# Digital_to_Analog.net
KiCad netlist of a schematic drawn in Altium Designer
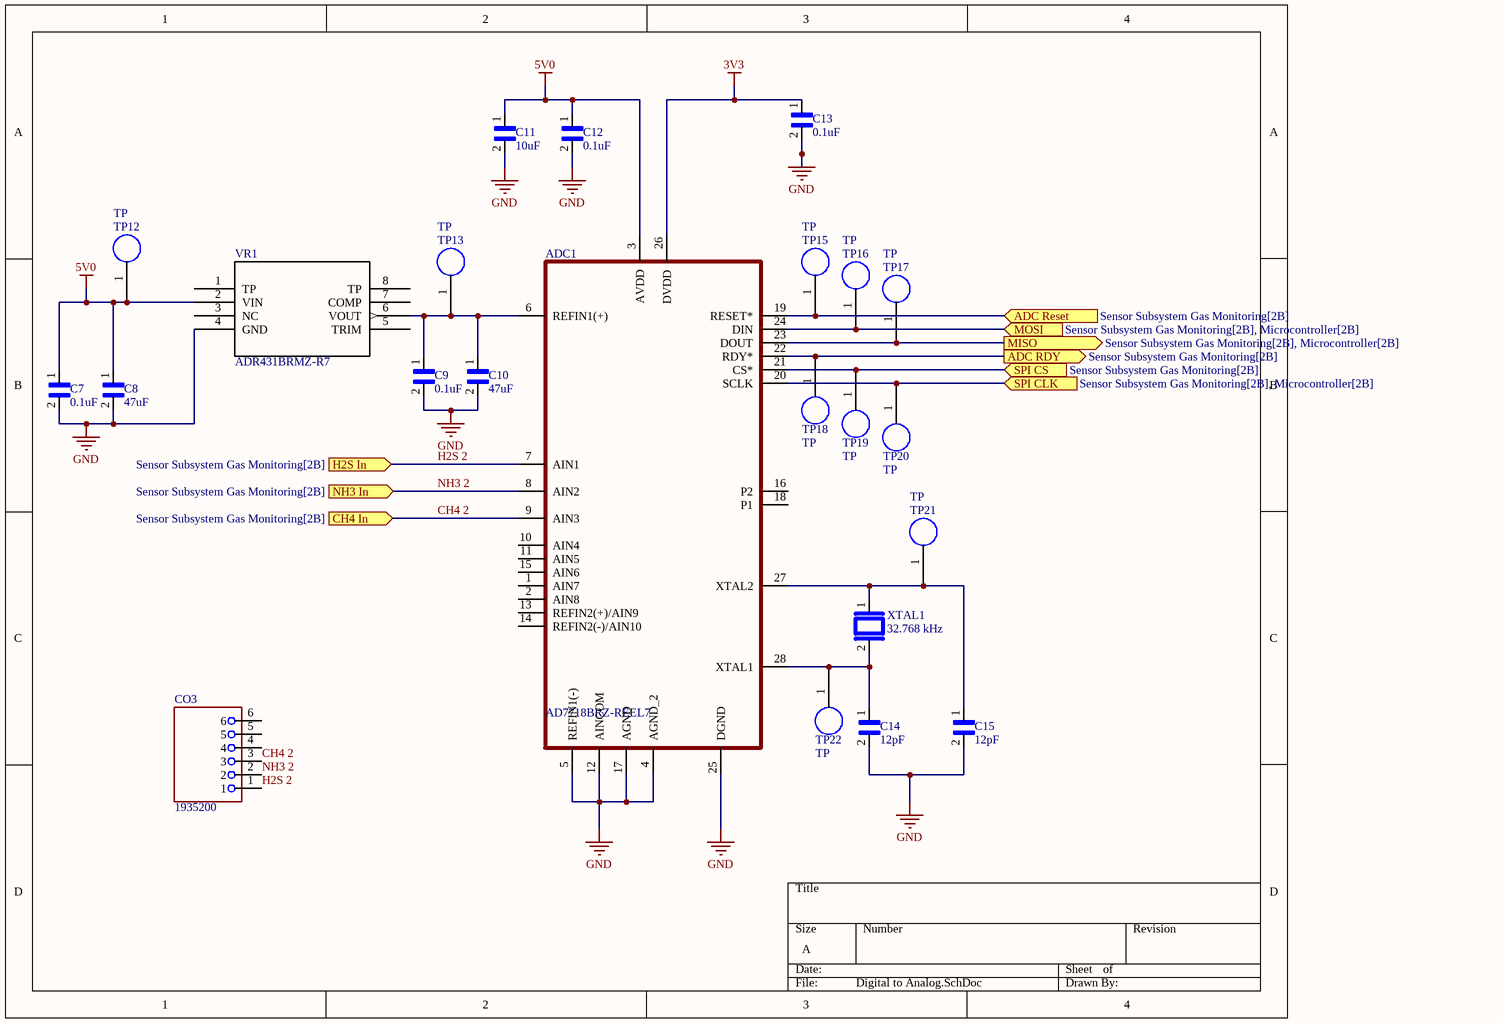
[diagram p0: Digital to Analog.SchDoc]

(export (version "E")
  (design (tool "Eeschema 10.0.6"))
  (components
    (comp (ref "ADC1")
      (value "AD7718BRZ-REEL7")
      (footprint "SOIC127P1032X265-28N")
      (description "24-Bit, 8/10-Channel, Low Voltage, Low Power, Sigma Delta ADC")
      (fields (field (name "MF") "Analog Devices"))
      (libsource (lib "AD7718") (part "AD7718BRZ-REEL7"))
    )
    (comp (ref "C7")
      (value "0.1uF")
      (footprint "0.1uF Capacitor")
      (description "No Description Available")
      (libsource (lib "0.1uF Capacitor") (part "CC1206JRX7R9BB104"))
    )
    (comp (ref "C8")
      (value "47uF")
      (footprint "47uF Capacitor:CAPC2012X135N")
      (description "47ÂµF Â±20% 6.3V Ceramic Capacitor X5R 0805 _2012 Metric_")
      (fields
        (field (name "MF") "Samsung Electro-Mechanics")
        (field (name "DIGI-KEY_PART_NUMBER") "1276-6467-1-ND")
      )
      (libsource (lib "47uF Capacitor") (part "CL21A476MQYNNNG"))
    )
    (comp (ref "C9")
      (value "0.1uF")
      (footprint "0.1uF Capacitor")
      (description "No Description Available")
      (libsource (lib "0.1uF Capacitor") (part "CC1206JRX7R9BB104"))
    )
    (comp (ref "C10")
      (value "47uF")
      (footprint "47uF Capacitor:CAPC2012X135N")
      (description "47ÂµF Â±20% 6.3V Ceramic Capacitor X5R 0805 _2012 Metric_")
      (fields
        (field (name "MF") "Samsung Electro-Mechanics")
        (field (name "DIGI-KEY_PART_NUMBER") "1276-6467-1-ND")
      )
      (libsource (lib "47uF Capacitor") (part "CL21A476MQYNNNG"))
    )
    (comp (ref "C11")
      (value "10uF")
      (footprint "10uF Capacitor:CAPC3216X190N")
      (description "CAP CER 10UF 25V X5R 1206")
      (fields (field (name "MP") "GRJ31CR61E106KE11L"))
      (libsource (lib "10uF Capacitor") (part "GRJ31CR61E106KE11L"))
    )
    (comp (ref "C12")
      (value "0.1uF")
      (footprint "0.1uF Capacitor")
      (description "No Description Available")
      (libsource (lib "0.1uF Capacitor") (part "CC1206JRX7R9BB104"))
    )
    (comp (ref "C13")
      (value "0.1uF")
      (footprint "0.1uF Capacitor")
      (description "No Description Available")
      (libsource (lib "0.1uF Capacitor") (part "CC1206JRX7R9BB104"))
    )
    (comp (ref "C14")
      (value "12pF")
      (footprint "CAPC1608X90N")
      (description "Multilayer Ceramic Capacitor, CGA Series, 12 pF, - 5%, C0G / NP0, 50 V, 0603 [1608 Metric]")
      (fields (field (name "MF") "TDK") (field (name "MP") "CGA3E2C0G1H120J080AA"))
      (libsource (lib "12pF Capacitor") (part "CGA3E2C0G1H120J080AA"))
    )
    (comp (ref "C15")
      (value "12pF")
      (footprint "CAPC1608X90N")
      (description "Multilayer Ceramic Capacitor, CGA Series, 12 pF, - 5%, C0G / NP0, 50 V, 0603 [1608 Metric]")
      (fields (field (name "MF") "TDK") (field (name "MP") "CGA3E2C0G1H120J080AA"))
      (libsource (lib "12pF Capacitor") (part "CGA3E2C0G1H120J080AA"))
    )
    (comp (ref "CO3")
      (value "1935200")
      (footprint "PHOENIX_1935200")
      (fields (field (name "MF") "Littelfuse"))
      (libsource (lib "Main Connector") (part "1935200"))
    )
    (comp (ref "TP12")
      (value "TP")
      (footprint "TestPoint")
      (description "Test point for voltage, current, ect.")
      (libsource (lib "TestPoint") (part "TestPoint"))
    )
    (comp (ref "TP13")
      (value "TP")
      (footprint "TestPoint")
      (description "Test point for voltage, current, ect.")
      (libsource (lib "TestPoint") (part "TestPoint"))
    )
    (comp (ref "TP15")
      (value "TP")
      (footprint "TestPoint")
      (description "Test point for voltage, current, ect.")
      (libsource (lib "TestPoint") (part "TestPoint"))
    )
    (comp (ref "TP16")
      (value "TP")
      (footprint "TestPoint")
      (description "Test point for voltage, current, ect.")
      (libsource (lib "TestPoint") (part "TestPoint"))
    )
    (comp (ref "TP17")
      (value "TP")
      (footprint "TestPoint")
      (description "Test point for voltage, current, ect.")
      (libsource (lib "TestPoint") (part "TestPoint"))
    )
    (comp (ref "TP18")
      (value "TP")
      (footprint "TestPoint")
      (description "Test point for voltage, current, ect.")
      (libsource (lib "TestPoint") (part "TestPoint"))
    )
    (comp (ref "TP19")
      (value "TP")
      (footprint "TestPoint")
      (description "Test point for voltage, current, ect.")
      (libsource (lib "TestPoint") (part "TestPoint"))
    )
    (comp (ref "TP20")
      (value "TP")
      (footprint "TestPoint")
      (description "Test point for voltage, current, ect.")
      (libsource (lib "TestPoint") (part "TestPoint"))
    )
    (comp (ref "TP21")
      (value "TP")
      (footprint "TestPoint")
      (description "Test point for voltage, current, ect.")
      (libsource (lib "TestPoint") (part "TestPoint"))
    )
    (comp (ref "TP22")
      (value "TP")
      (footprint "TestPoint")
      (description "Test point for voltage, current, ect.")
      (libsource (lib "TestPoint") (part "TestPoint"))
    )
    (comp (ref "VR1")
      (value "ADR431BRMZ-R7")
      (footprint "RM_8_ADI")
      (description "No Description Available")
      (libsource (lib "Voltage Reference") (part "ADR431BRMZ-R7"))
    )
    (comp (ref "XTAL1")
      (value "32.768 kHz")
      (footprint "XTAL_ABS07-32.768KHZ-T")
      (description "32.768 kHz Â±20ppm Crystal 12.5pF 70 kOhms 2-SMD, No Lead")
      (fields (field (name "MP") "ABS07-32.768KHZ-T") (field (name "MF") "Abracon"))
      (libsource (lib "Watch Crystal") (part "ABS07-32.768KHZ-T"))
    )
  )
  (nets
    (net (code "1") (name "/ADC RDY") (class "Default")
      (node (ref "ADC1") (pin "22") (pinfunction "RDY*_22") (pintype "passive"))
      (node (ref "TP18") (pin "1") (pintype "passive"))
    )
    (net (code "2") (name "/ADC Reset") (class "Default")
      (node (ref "ADC1") (pin "19") (pinfunction "RESET*_19") (pintype "passive"))
      (node (ref "TP15") (pin "1") (pintype "passive"))
    )
    (net (code "3") (name "/CH4 2") (class "Default")
      (node (ref "ADC1") (pin "9") (pinfunction "AIN3_9") (pintype "passive"))
      (node (ref "CO3") (pin "3") (pinfunction "3_3") (pintype "passive"))
    )
    (net (code "4") (name "/H2S 2") (class "Default")
      (node (ref "ADC1") (pin "7") (pinfunction "AIN1_7") (pintype "passive"))
      (node (ref "CO3") (pin "1") (pinfunction "1_1") (pintype "passive"))
    )
    (net (code "5") (name "/MISO") (class "Default")
      (node (ref "ADC1") (pin "23") (pinfunction "DOUT_23") (pintype "passive"))
      (node (ref "TP17") (pin "1") (pintype "passive"))
    )
    (net (code "6") (name "/MOSI") (class "Default")
      (node (ref "ADC1") (pin "24") (pinfunction "DIN_24") (pintype "passive"))
      (node (ref "TP16") (pin "1") (pintype "passive"))
    )
    (net (code "7") (name "/NH3 2") (class "Default")
      (node (ref "ADC1") (pin "8") (pinfunction "AIN2_8") (pintype "passive"))
      (node (ref "CO3") (pin "2") (pinfunction "2_2") (pintype "passive"))
    )
    (net (code "8") (name "/SPI CLK") (class "Default")
      (node (ref "ADC1") (pin "20") (pinfunction "SCLK_20") (pintype "passive"))
      (node (ref "TP20") (pin "1") (pintype "passive"))
    )
    (net (code "9") (name "/SPI CS") (class "Default")
      (node (ref "ADC1") (pin "21") (pinfunction "CS*_21") (pintype "passive"))
      (node (ref "TP19") (pin "1") (pintype "passive"))
    )
    (net (code "10") (name "3V3") (class "Default")
      (node (ref "ADC1") (pin "26") (pinfunction "DVDD_26") (pintype "power_in"))
      (node (ref "C13") (pin "1") (pintype "passive"))
    )
    (net (code "11") (name "5V0") (class "Default")
      (node (ref "ADC1") (pin "3") (pinfunction "AVDD_3") (pintype "power_in"))
      (node (ref "C11") (pin "1") (pinfunction "1_1") (pintype "passive"))
      (node (ref "C12") (pin "1") (pintype "passive"))
      (node (ref "C7") (pin "1") (pintype "passive"))
      (node (ref "C8") (pin "1") (pinfunction "1_1") (pintype "passive"))
      (node (ref "TP12") (pin "1") (pintype "passive"))
      (node (ref "VR1") (pin "2") (pinfunction "VIN_2") (pintype "passive"))
    )
    (net (code "12") (name "GND") (class "Default")
      (node (ref "ADC1") (pin "12") (pinfunction "AINCOM_12") (pintype "passive"))
      (node (ref "ADC1") (pin "17") (pinfunction "AGND_17") (pintype "passive"))
      (node (ref "ADC1") (pin "25") (pinfunction "DGND_25") (pintype "passive"))
      (node (ref "ADC1") (pin "4") (pinfunction "AGND_2_4") (pintype "passive"))
      (node (ref "ADC1") (pin "5") (pinfunction "REFIN1(-)_5") (pintype "passive"))
      (node (ref "C10") (pin "2") (pinfunction "2_2") (pintype "passive"))
      (node (ref "C11") (pin "2") (pinfunction "2_2") (pintype "passive"))
      (node (ref "C12") (pin "2") (pintype "passive"))
      (node (ref "C13") (pin "2") (pintype "passive"))
      (node (ref "C14") (pin "2") (pintype "passive"))
      (node (ref "C15") (pin "2") (pintype "passive"))
      (node (ref "C7") (pin "2") (pintype "passive"))
      (node (ref "C8") (pin "2") (pinfunction "2_2") (pintype "passive"))
      (node (ref "C9") (pin "2") (pintype "passive"))
      (node (ref "VR1") (pin "4") (pinfunction "GND_4") (pintype "power_in"))
    )
    (net (code "13") (name "Net-(ADC1-REFIN1(+))") (class "Default")
      (node (ref "ADC1") (pin "6") (pinfunction "REFIN1(+)_6") (pintype "passive"))
      (node (ref "C10") (pin "1") (pinfunction "1_1") (pintype "passive"))
      (node (ref "C9") (pin "1") (pintype "passive"))
      (node (ref "TP13") (pin "1") (pintype "passive"))
      (node (ref "VR1") (pin "6") (pinfunction "VOUT_6") (pintype "output"))
    )
    (net (code "14") (name "Net-(ADC1-XTAL1)") (class "Default")
      (node (ref "ADC1") (pin "28") (pinfunction "XTAL1_28") (pintype "passive"))
      (node (ref "C14") (pin "1") (pintype "passive"))
      (node (ref "TP22") (pin "1") (pintype "passive"))
      (node (ref "XTAL1") (pin "2") (pinfunction "2_2") (pintype "passive"))
    )
    (net (code "15") (name "Net-(ADC1-XTAL2)") (class "Default")
      (node (ref "ADC1") (pin "27") (pinfunction "XTAL2_27") (pintype "passive"))
      (node (ref "C15") (pin "1") (pintype "passive"))
      (node (ref "TP21") (pin "1") (pintype "passive"))
      (node (ref "XTAL1") (pin "1") (pinfunction "1_1") (pintype "passive"))
    )
    (net (code "16") (name "unconnected-(ADC1-AIN4-Pad10)") (class "Default")
      (node (ref "ADC1") (pin "10") (pinfunction "AIN4_10") (pintype "passive"))
    )
    (net (code "17") (name "unconnected-(ADC1-AIN5-Pad11)") (class "Default")
      (node (ref "ADC1") (pin "11") (pinfunction "AIN5_11") (pintype "passive"))
    )
    (net (code "18") (name "unconnected-(ADC1-AIN6-Pad15)") (class "Default")
      (node (ref "ADC1") (pin "15") (pinfunction "AIN6_15") (pintype "passive"))
    )
    (net (code "19") (name "unconnected-(ADC1-AIN7-Pad1)") (class "Default")
      (node (ref "ADC1") (pin "1") (pinfunction "AIN7_1") (pintype "passive"))
    )
    (net (code "20") (name "unconnected-(ADC1-AIN8-Pad2)") (class "Default")
      (node (ref "ADC1") (pin "2") (pinfunction "AIN8_2") (pintype "passive"))
    )
    (net (code "21") (name "unconnected-(ADC1-P1-Pad18)") (class "Default")
      (node (ref "ADC1") (pin "18") (pinfunction "P1_18") (pintype "passive"))
    )
    (net (code "22") (name "unconnected-(ADC1-P2-Pad16)") (class "Default")
      (node (ref "ADC1") (pin "16") (pinfunction "P2_16") (pintype "passive"))
    )
    (net (code "23") (name "unconnected-(ADC1-REFIN2(+){slash}AIN9-Pad13)") (class "Default")
      (node (ref "ADC1") (pin "13") (pinfunction "REFIN2(+)/AIN9_13") (pintype "passive"))
    )
    (net (code "24") (name "unconnected-(ADC1-REFIN2(-){slash}AIN10-Pad14)") (class "Default")
      (node (ref "ADC1") (pin "14") (pinfunction "REFIN2(-)/AIN10_14") (pintype "passive"))
    )
    (net (code "25") (name "unconnected-(CO3-Pad4)") (class "Default")
      (node (ref "CO3") (pin "4") (pinfunction "4_4") (pintype "passive"))
    )
    (net (code "26") (name "unconnected-(CO3-Pad5)") (class "Default")
      (node (ref "CO3") (pin "5") (pinfunction "5_5") (pintype "passive"))
    )
    (net (code "27") (name "unconnected-(CO3-Pad6)") (class "Default")
      (node (ref "CO3") (pin "6") (pinfunction "6_6") (pintype "passive"))
    )
    (net (code "28") (name "unconnected-(VR1-COMP-Pad7)") (class "Default")
      (node (ref "VR1") (pin "7") (pinfunction "COMP_7") (pintype "passive"))
    )
    (net (code "29") (name "unconnected-(VR1-NC-Pad3)") (class "Default")
      (node (ref "VR1") (pin "3") (pinfunction "NC_3") (pintype "passive"))
    )
    (net (code "30") (name "unconnected-(VR1-TP-Pad1)") (class "Default")
      (node (ref "VR1") (pin "1") (pinfunction "TP_1") (pintype "passive"))
    )
    (net (code "31") (name "unconnected-(VR1-TP-Pad8)") (class "Default")
      (node (ref "VR1") (pin "8") (pinfunction "TP_8") (pintype "passive"))
    )
    (net (code "32") (name "unconnected-(VR1-TRIM-Pad5)") (class "Default")
      (node (ref "VR1") (pin "5") (pinfunction "TRIM_5") (pintype "passive"))
    )
  )
)
